# Main_Connectors.net
KiCad netlist of a schematic drawn in Altium Designer
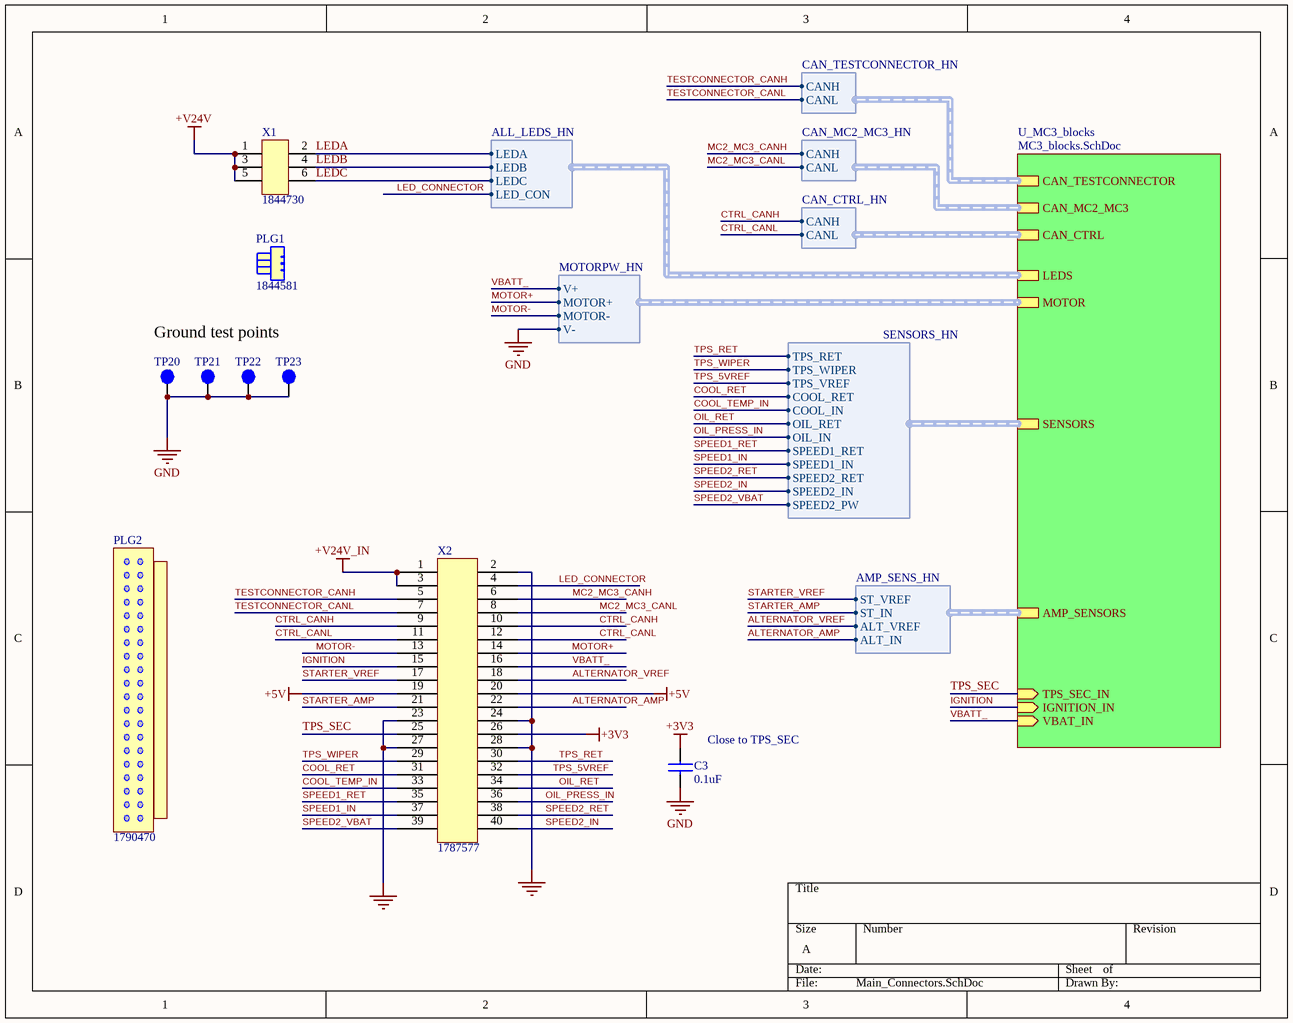
[diagram p0: Main_Connectors.SchDoc]

(export (version "E")
  (design (tool "Eeschema 10.0.6"))
  (components
    (comp (ref "C3")
      (value "0.1uF")
      (footprint "C0805")
      (description "Cap Ceramic 0.1uF 50V X7R 10% SMD 2.0 x 1.2 mm 125 C Paper T/R")
      (fields
        (field (name "MANUFACTURER") "KEMET")
        (field (name "MANUFACTURER PART NUMBER") "C0805C104K5RACTU")
      )
      (libsource (lib "MCx") (part "C0805C104K5RACTU"))
    )
    (comp (ref "PLG1")
      (value "1844581")
      (description "Terminal block; plug; 6 positions; 0.100\"(2.54mm) pitch; Screwless; 6A; 150V; Black")
      (fields (field (name "MANUFACTURER") "Phoenix Contact") (field (name "VOLTAGE") "150V"))
      (libsource (lib "MCx") (part "1844581"))
    )
    (comp (ref "PLG2")
      (value "1790470")
      (description "40 position; 8A; 250V; Push-in;Terminal block; PCB; Plug; Female Sockets;")
      (fields (field (name "MANUFACTURER") "Phoenix Contact") (field (name "VOLTAGE") "150V"))
      (libsource (lib "MCx") (part "1790470"))
    )
    (comp (ref "TP20")
      (value "T")
      (footprint "MC1:TESTPOINTSMD_1x1MM")
      (description "SMD Test Point")
      (libsource (lib "MC1") (part "TestPoint_SMD_1x1"))
    )
    (comp (ref "TP21")
      (value "T")
      (footprint "MC1:TESTPOINTSMD_1x1MM")
      (description "SMD Test Point")
      (libsource (lib "MC1") (part "TestPoint_SMD_1x1"))
    )
    (comp (ref "TP22")
      (value "T")
      (footprint "MC1:TESTPOINTSMD_1x1MM")
      (description "SMD Test Point")
      (libsource (lib "MC1") (part "TestPoint_SMD_1x1"))
    )
    (comp (ref "TP23")
      (value "T")
      (footprint "MC1:TESTPOINTSMD_1x1MM")
      (description "SMD Test Point")
      (libsource (lib "MC1") (part "TestPoint_SMD_1x1"))
    )
    (comp (ref "X1")
      (value "1844730")
      (footprint "DMC 0,5/ 3-G1- 2,54 P20THR R24")
      (description "Terminal block; Header; Male Pins; (4 Side); 6 pos; 0.100\"(2.54mm) pitch; 6A; 150V")
      (fields (field (name "MANUFACTURER") "Phoenix Contact") (field (name "VOLTAGE") "150V"))
      (libsource (lib "MCx") (part "1844730"))
    )
    (comp (ref "X2")
      (value "1787577")
      (footprint "DMCV 1,5/20-G1F-3,5-LR P20THR")
      (description "40 pins PCB header Phoenix Contact 1787577 Contact spacing: 3.50 mm")
      (fields (field (name "MANUFACTURER") "Phoenix Contact") (field (name "VOLTAGE") "150V"))
      (libsource (lib "MCx") (part "1787577"))
    )
  )
  (nets
    (net (code "8") (name "+3V3") (class "Default")
      (node (ref "C3") (pin "1") (pinfunction "1_1") (pintype "passive"))
      (node (ref "X2") (pin "26") (pintype "passive"))
    )
    (net (code "9") (name "+5V") (class "Default")
      (node (ref "X2") (pin "19") (pintype "passive"))
      (node (ref "X2") (pin "20") (pintype "passive"))
    )
    (net (code "10") (name "+V24V") (class "Default")
      (node (ref "X1") (pin "1") (pintype "passive"))
      (node (ref "X1") (pin "3") (pintype "passive"))
      (node (ref "X1") (pin "5") (pintype "passive"))
    )
    (net (code "11") (name "+V24V_IN") (class "Default")
      (node (ref "X2") (pin "1") (pintype "passive"))
      (node (ref "X2") (pin "3") (pintype "passive"))
    )
    (net (code "12") (name "/ALTERNATOR_AMP") (class "Default")
      (node (ref "X2") (pin "22") (pintype "passive"))
    )
    (net (code "13") (name "/ALTERNATOR_VREF") (class "Default")
      (node (ref "X2") (pin "18") (pintype "passive"))
    )
    (net (code "14") (name "/COOL_RET") (class "Default") (node (ref "X2") (pin "31") (pintype "passive")))
    (net (code "15") (name "/COOL_TEMP_IN") (class "Default")
      (node (ref "X2") (pin "33") (pintype "passive"))
    )
    (net (code "16") (name "/CTRL_CANH") (class "Default")
      (node (ref "X2") (pin "10") (pintype "passive"))
      (node (ref "X2") (pin "9") (pintype "passive"))
    )
    (net (code "17") (name "/CTRL_CANL") (class "Default")
      (node (ref "X2") (pin "11") (pintype "passive"))
      (node (ref "X2") (pin "12") (pintype "passive"))
    )
    (net (code "18") (name "/IGNITION") (class "Default") (node (ref "X2") (pin "15") (pintype "passive")))
    (net (code "19") (name "/LEDA") (class "Default") (node (ref "X1") (pin "2") (pintype "passive")))
    (net (code "20") (name "/LEDB") (class "Default") (node (ref "X1") (pin "4") (pintype "passive")))
    (net (code "21") (name "/LEDC") (class "Default") (node (ref "X1") (pin "6") (pintype "passive")))
    (net (code "22") (name "/LED_CONNECTOR") (class "Default")
      (node (ref "X2") (pin "4") (pintype "passive"))
    )
    (net (code "23") (name "/MC2_MC3_CANH") (class "Default") (node (ref "X2") (pin "6") (pintype "passive")))
    (net (code "24") (name "/MC2_MC3_CANL") (class "Default") (node (ref "X2") (pin "8") (pintype "passive")))
    (net (code "25") (name "/MOTOR+") (class "Default") (node (ref "X2") (pin "14") (pintype "passive")))
    (net (code "26") (name "/MOTOR-") (class "Default") (node (ref "X2") (pin "13") (pintype "passive")))
    (net (code "27") (name "/OIL_PRESS_IN") (class "Default")
      (node (ref "X2") (pin "36") (pintype "passive"))
    )
    (net (code "28") (name "/OIL_RET") (class "Default") (node (ref "X2") (pin "34") (pintype "passive")))
    (net (code "29") (name "/SPEED1_IN") (class "Default") (node (ref "X2") (pin "37") (pintype "passive")))
    (net (code "30") (name "/SPEED1_RET") (class "Default") (node (ref "X2") (pin "35") (pintype "passive")))
    (net (code "31") (name "/SPEED2_IN") (class "Default") (node (ref "X2") (pin "40") (pintype "passive")))
    (net (code "32") (name "/SPEED2_RET") (class "Default") (node (ref "X2") (pin "38") (pintype "passive")))
    (net (code "33") (name "/SPEED2_VBAT") (class "Default") (node (ref "X2") (pin "39") (pintype "passive")))
    (net (code "34") (name "/STARTER_AMP") (class "Default") (node (ref "X2") (pin "21") (pintype "passive")))
    (net (code "35") (name "/STARTER_VREF") (class "Default")
      (node (ref "X2") (pin "17") (pintype "passive"))
    )
    (net (code "36") (name "/TESTCONNECTOR_CANH") (class "Default")
      (node (ref "X2") (pin "5") (pintype "passive"))
    )
    (net (code "37") (name "/TESTCONNECTOR_CANL") (class "Default")
      (node (ref "X2") (pin "7") (pintype "passive"))
    )
    (net (code "38") (name "/TPS_5VREF") (class "Default") (node (ref "X2") (pin "32") (pintype "passive")))
    (net (code "39") (name "/TPS_RET") (class "Default") (node (ref "X2") (pin "30") (pintype "passive")))
    (net (code "40") (name "/TPS_SEC") (class "Default") (node (ref "X2") (pin "25") (pintype "passive")))
    (net (code "41") (name "/TPS_WIPER") (class "Default") (node (ref "X2") (pin "29") (pintype "passive")))
    (net (code "42") (name "/VBATT_") (class "Default") (node (ref "X2") (pin "16") (pintype "passive")))
    (net (code "50") (name "GND") (class "Default")
      (node (ref "C3") (pin "2") (pinfunction "2_2") (pintype "passive"))
      (node (ref "TP20") (pin "1") (pinfunction "1_1") (pintype "passive"))
      (node (ref "TP21") (pin "1") (pinfunction "1_1") (pintype "passive"))
      (node (ref "TP22") (pin "1") (pinfunction "1_1") (pintype "passive"))
      (node (ref "TP23") (pin "1") (pinfunction "1_1") (pintype "passive"))
      (node (ref "X2") (pin "2") (pintype "passive"))
      (node (ref "X2") (pin "23") (pintype "passive"))
      (node (ref "X2") (pin "24") (pintype "passive"))
      (node (ref "X2") (pin "27") (pintype "passive"))
      (node (ref "X2") (pin "28") (pintype "passive"))
    )
  )
)
